# CapstoneGroup9.net
KiCad netlist of a schematic drawn in EAGLE
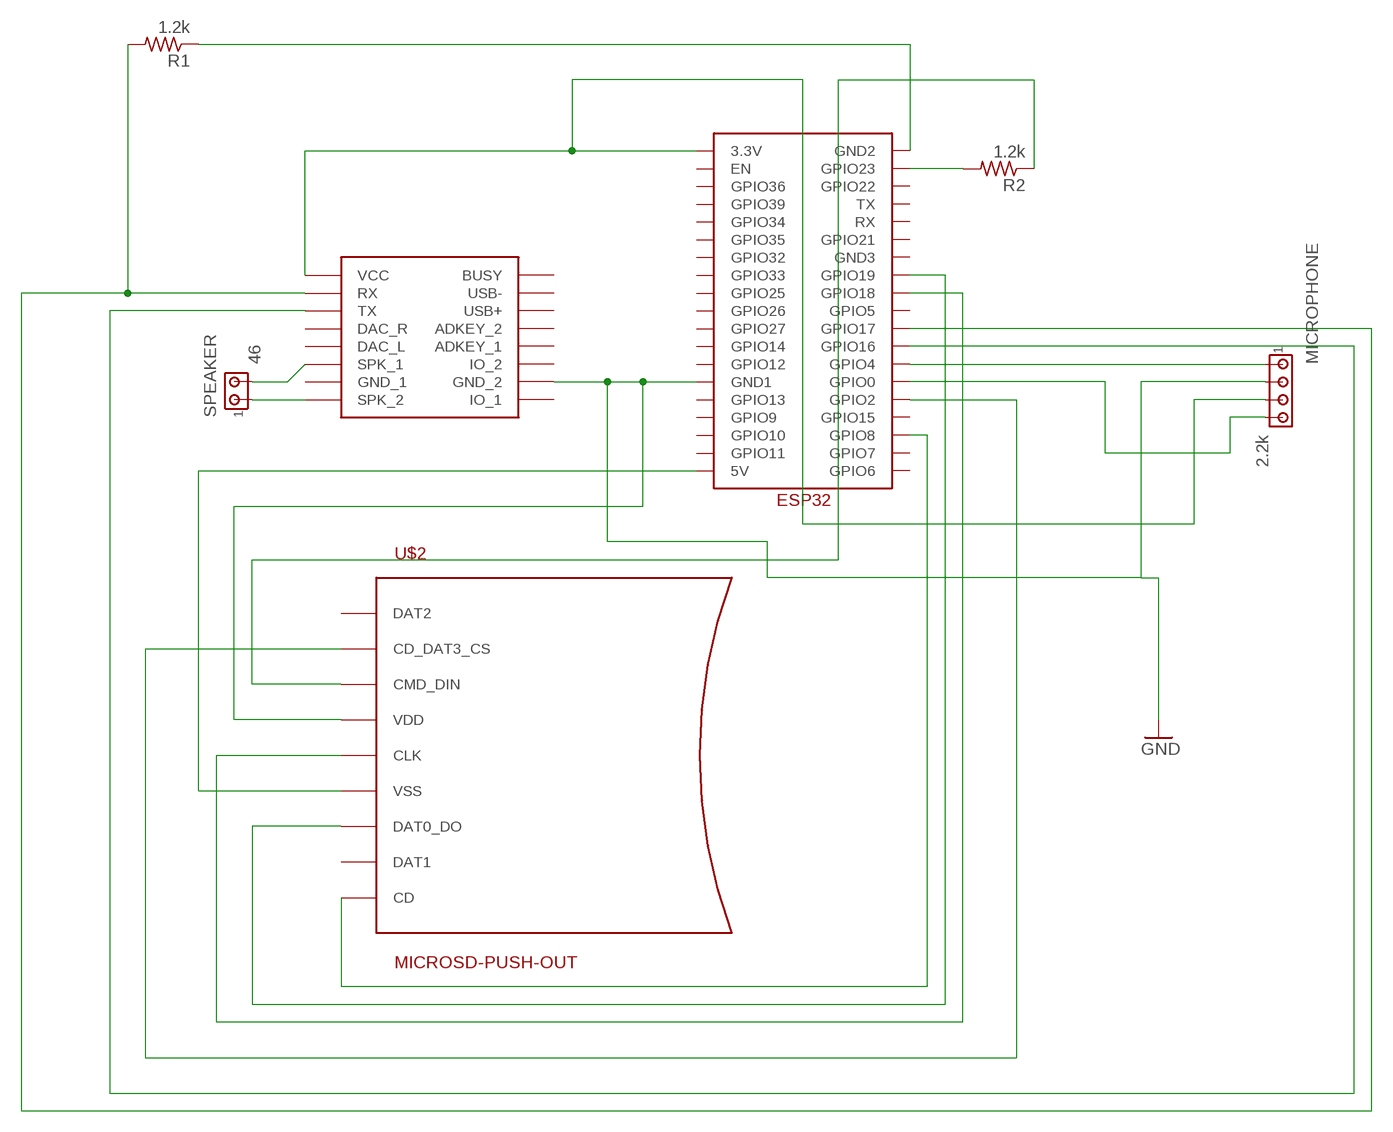
[diagram p0: schematic, sheet 1]

(export (version "E")
  (design (tool "Eeschema 10.0.6"))
  (components
    (comp (ref "DFPLAYERMINI")
      (value "DFPLAYER")
      (footprint "eagle-import:DFPLAYER")
      (libsource (lib "eagle-import") (part "DFPLAYER"))
    )
    (comp (ref "MICROPHONE")
      (value "2.2k")
      (footprint "eagle-import:10X04MTA")
      (libsource (lib "eagle-import") (part "MTA04-100"))
    )
    (comp (ref "R1")
      (value "1.2k")
      (footprint "eagle-import:0207_10")
      (libsource (lib "eagle-import") (part "R-US_0207/10"))
    )
    (comp (ref "R2")
      (value "1.2k")
      (footprint "eagle-import:0207_10")
      (libsource (lib "eagle-import") (part "R-US_0207/10"))
    )
    (comp (ref "SPEAKER")
      (value "46")
      (footprint "eagle-import:10X02MTA")
      (libsource (lib "eagle-import") (part "MTA02-100"))
    )
    (comp (ref "U$1")
      (value "ESP32")
      (footprint "eagle-import:ESP32")
      (libsource (lib "eagle-import") (part "ESP32"))
    )
    (comp (ref "U$2")
      (value "MICROSD-PUSH-OUT")
      (footprint "eagle-import:MICROSD-PUSH-OUT")
      (libsource (lib "eagle-import") (part "MICROSD-PUSH-OUT"))
    )
  )
  (nets
    (net (code "1") (name "GND") (class "Default")
      (node (ref "DFPLAYERMINI") (pin "GND_2") (pinfunction "GND_2_GND_2") (pintype "bidirectional"))
      (node (ref "MICROPHONE") (pin "2") (pinfunction "2_2") (pintype "passive"))
      (node (ref "U$1") (pin "GND1") (pinfunction "GND1_GND1") (pintype "bidirectional"))
      (node (ref "U$2") (pin "4") (pinfunction "VDD_4") (pintype "bidirectional"))
    )
    (net (code "2") (name "Net-(DFPLAYERMINI-PadRX)") (class "Default")
      (node (ref "DFPLAYERMINI") (pin "RX") (pinfunction "RX_RX") (pintype "bidirectional"))
      (node (ref "R1") (pin "2") (pinfunction "2_2") (pintype "passive"))
      (node (ref "U$1") (pin "GPIO17") (pinfunction "GPIO17_GPIO17") (pintype "bidirectional"))
    )
    (net (code "3") (name "Net-(DFPLAYERMINI-PadTX)") (class "Default")
      (node (ref "DFPLAYERMINI") (pin "TX") (pinfunction "TX_TX") (pintype "bidirectional"))
      (node (ref "U$1") (pin "GPIO16") (pinfunction "GPIO16_GPIO16") (pintype "bidirectional"))
    )
    (net (code "4") (name "Net-(DFPLAYERMINI-PadVCC)") (class "Default")
      (node (ref "DFPLAYERMINI") (pin "VCC") (pinfunction "VCC_VCC") (pintype "bidirectional"))
      (node (ref "MICROPHONE") (pin "3") (pinfunction "3_3") (pintype "passive"))
      (node (ref "U$1") (pin "3.3V") (pinfunction "3.3V_3.3V") (pintype "bidirectional"))
    )
    (net (code "5") (name "Net-(DFPLAYERMINI-SPK_1)") (class "Default")
      (node (ref "DFPLAYERMINI") (pin "SPK1") (pinfunction "SPK_1_SPK1") (pintype "bidirectional"))
      (node (ref "SPEAKER") (pin "2") (pinfunction "2_2") (pintype "passive"))
    )
    (net (code "6") (name "Net-(DFPLAYERMINI-SPK_2)") (class "Default")
      (node (ref "DFPLAYERMINI") (pin "SPK2") (pinfunction "SPK_2_SPK2") (pintype "bidirectional"))
      (node (ref "SPEAKER") (pin "1") (pinfunction "1_1") (pintype "passive"))
    )
    (net (code "7") (name "Net-(MICROPHONE-Pad1)") (class "Default")
      (node (ref "MICROPHONE") (pin "1") (pinfunction "1_1") (pintype "passive"))
      (node (ref "U$1") (pin "GPIO4") (pinfunction "GPIO4_GPIO4") (pintype "bidirectional"))
    )
    (net (code "8") (name "Net-(MICROPHONE-Pad4)") (class "Default")
      (node (ref "MICROPHONE") (pin "4") (pinfunction "4_4") (pintype "passive"))
      (node (ref "U$1") (pin "GPIO0") (pinfunction "GPIO0_GPIO0") (pintype "bidirectional"))
    )
    (net (code "9") (name "Net-(R1-Pad1)") (class "Default")
      (node (ref "R1") (pin "1") (pinfunction "1_1") (pintype "passive"))
      (node (ref "U$1") (pin "GND2") (pinfunction "GND2_GND2") (pintype "bidirectional"))
    )
    (net (code "10") (name "Net-(R2-Pad2)") (class "Default")
      (node (ref "R2") (pin "2") (pinfunction "2_2") (pintype "passive"))
      (node (ref "U$1") (pin "GPIO23") (pinfunction "GPIO23_GPIO23") (pintype "bidirectional"))
    )
    (net (code "11") (name "Net-(U$1-Pad5V)") (class "Default")
      (node (ref "U$1") (pin "5V") (pinfunction "5V_5V") (pintype "bidirectional"))
      (node (ref "U$2") (pin "6") (pinfunction "VSS_6") (pintype "bidirectional"))
      (node (ref "U$2") (pin "G1") (pinfunction "VSS_G1") (pintype "bidirectional"))
      (node (ref "U$2") (pin "G2") (pinfunction "VSS_G2") (pintype "bidirectional"))
      (node (ref "U$2") (pin "G3") (pinfunction "VSS_G3") (pintype "bidirectional"))
      (node (ref "U$2") (pin "G4") (pinfunction "VSS_G4") (pintype "bidirectional"))
    )
    (net (code "12") (name "Net-(U$1-PadGPIO8)") (class "Default")
      (node (ref "U$1") (pin "GPIO8") (pinfunction "GPIO8_GPIO8") (pintype "bidirectional"))
      (node (ref "U$2") (pin "CD") (pinfunction "CD_CD") (pintype "bidirectional"))
    )
    (net (code "13") (name "Net-(U$2-CD_DAT3_CS)") (class "Default")
      (node (ref "U$1") (pin "GPIO2") (pinfunction "GPIO2_GPIO2") (pintype "bidirectional"))
      (node (ref "U$2") (pin "2") (pinfunction "CD_DAT3_CS_2") (pintype "bidirectional"))
    )
    (net (code "14") (name "Net-(U$2-CLK)") (class "Default")
      (node (ref "U$1") (pin "GPIO18") (pinfunction "GPIO18_GPIO18") (pintype "bidirectional"))
      (node (ref "U$2") (pin "5") (pinfunction "CLK_5") (pintype "bidirectional"))
    )
    (net (code "15") (name "Net-(U$2-CMD_DIN)") (class "Default")
      (node (ref "R2") (pin "1") (pinfunction "1_1") (pintype "passive"))
      (node (ref "U$2") (pin "3") (pinfunction "CMD_DIN_3") (pintype "bidirectional"))
    )
    (net (code "16") (name "Net-(U$2-DAT0_DO)") (class "Default")
      (node (ref "U$1") (pin "GPIO19") (pinfunction "GPIO19_GPIO19") (pintype "bidirectional"))
      (node (ref "U$2") (pin "7") (pinfunction "DAT0_DO_7") (pintype "bidirectional"))
    )
    (net (code "17") (name "unconnected-(DFPLAYERMINI-ADKEY_1-PadADKEY1)") (class "Default")
      (node (ref "DFPLAYERMINI") (pin "ADKEY1") (pinfunction "ADKEY_1_ADKEY1") (pintype "bidirectional"))
    )
    (net (code "18") (name "unconnected-(DFPLAYERMINI-ADKEY_2-PadADKEY2)") (class "Default")
      (node (ref "DFPLAYERMINI") (pin "ADKEY2") (pinfunction "ADKEY_2_ADKEY2") (pintype "bidirectional"))
    )
    (net (code "19") (name "unconnected-(DFPLAYERMINI-IO_1-PadIO1)") (class "Default")
      (node (ref "DFPLAYERMINI") (pin "IO1") (pinfunction "IO_1_IO1") (pintype "bidirectional"))
    )
    (net (code "20") (name "unconnected-(DFPLAYERMINI-IO_2-PadIO2)") (class "Default")
      (node (ref "DFPLAYERMINI") (pin "IO2") (pinfunction "IO_2_IO2") (pintype "bidirectional"))
    )
    (net (code "21") (name "unconnected-(DFPLAYERMINI-PadBUSY)") (class "Default")
      (node (ref "DFPLAYERMINI") (pin "BUSY") (pinfunction "BUSY_BUSY") (pintype "bidirectional"))
    )
    (net (code "22") (name "unconnected-(DFPLAYERMINI-PadDAC_L)") (class "Default")
      (node (ref "DFPLAYERMINI") (pin "DAC_L") (pinfunction "DAC_L_DAC_L") (pintype "bidirectional"))
    )
    (net (code "23") (name "unconnected-(DFPLAYERMINI-PadDAC_R)") (class "Default")
      (node (ref "DFPLAYERMINI") (pin "DAC_R") (pinfunction "DAC_R_DAC_R") (pintype "bidirectional"))
    )
    (net (code "24") (name "unconnected-(DFPLAYERMINI-PadGND_1)") (class "Default")
      (node (ref "DFPLAYERMINI") (pin "GND_1") (pinfunction "GND_1_GND_1") (pintype "bidirectional"))
    )
    (net (code "25") (name "unconnected-(DFPLAYERMINI-PadUSB+)") (class "Default")
      (node (ref "DFPLAYERMINI") (pin "USB+") (pinfunction "USB+_USB+") (pintype "bidirectional"))
    )
    (net (code "26") (name "unconnected-(DFPLAYERMINI-PadUSB-)") (class "Default")
      (node (ref "DFPLAYERMINI") (pin "USB-") (pinfunction "USB-_USB-") (pintype "bidirectional"))
    )
    (net (code "27") (name "unconnected-(U$1-PadEN)") (class "Default")
      (node (ref "U$1") (pin "EN") (pinfunction "EN_EN") (pintype "bidirectional"))
    )
    (net (code "28") (name "unconnected-(U$1-PadGND3)") (class "Default")
      (node (ref "U$1") (pin "GND3") (pinfunction "GND3_GND3") (pintype "bidirectional"))
    )
    (net (code "29") (name "unconnected-(U$1-PadGPIO5)") (class "Default")
      (node (ref "U$1") (pin "GPIO5") (pinfunction "GPIO5_GPIO5") (pintype "bidirectional"))
    )
    (net (code "30") (name "unconnected-(U$1-PadGPIO6)") (class "Default")
      (node (ref "U$1") (pin "GPIO6") (pinfunction "GPIO6_GPIO6") (pintype "bidirectional"))
    )
    (net (code "31") (name "unconnected-(U$1-PadGPIO7)") (class "Default")
      (node (ref "U$1") (pin "GPIO7") (pinfunction "GPIO7_GPIO7") (pintype "bidirectional"))
    )
    (net (code "32") (name "unconnected-(U$1-PadGPIO9)") (class "Default")
      (node (ref "U$1") (pin "GPIO9") (pinfunction "GPIO9_GPIO9") (pintype "bidirectional"))
    )
    (net (code "33") (name "unconnected-(U$1-PadGPIO10)") (class "Default")
      (node (ref "U$1") (pin "GPIO10") (pinfunction "GPIO10_GPIO10") (pintype "bidirectional"))
    )
    (net (code "34") (name "unconnected-(U$1-PadGPIO11)") (class "Default")
      (node (ref "U$1") (pin "GPIO11") (pinfunction "GPIO11_GPIO11") (pintype "bidirectional"))
    )
    (net (code "35") (name "unconnected-(U$1-PadGPIO12)") (class "Default")
      (node (ref "U$1") (pin "GPIO12") (pinfunction "GPIO12_GPIO12") (pintype "bidirectional"))
    )
    (net (code "36") (name "unconnected-(U$1-PadGPIO13)") (class "Default")
      (node (ref "U$1") (pin "GPIO13") (pinfunction "GPIO13_GPIO13") (pintype "bidirectional"))
    )
    (net (code "37") (name "unconnected-(U$1-PadGPIO14)") (class "Default")
      (node (ref "U$1") (pin "GPIO14") (pinfunction "GPIO14_GPIO14") (pintype "bidirectional"))
    )
    (net (code "38") (name "unconnected-(U$1-PadGPIO15)") (class "Default")
      (node (ref "U$1") (pin "GPIO15") (pinfunction "GPIO15_GPIO15") (pintype "bidirectional"))
    )
    (net (code "39") (name "unconnected-(U$1-PadGPIO21)") (class "Default")
      (node (ref "U$1") (pin "GPIO21") (pinfunction "GPIO21_GPIO21") (pintype "bidirectional"))
    )
    (net (code "40") (name "unconnected-(U$1-PadGPIO22)") (class "Default")
      (node (ref "U$1") (pin "GPIO22") (pinfunction "GPIO22_GPIO22") (pintype "bidirectional"))
    )
    (net (code "41") (name "unconnected-(U$1-PadGPIO25)") (class "Default")
      (node (ref "U$1") (pin "GPIO25") (pinfunction "GPIO25_GPIO25") (pintype "bidirectional"))
    )
    (net (code "42") (name "unconnected-(U$1-PadGPIO26)") (class "Default")
      (node (ref "U$1") (pin "GPIO26") (pinfunction "GPIO26_GPIO26") (pintype "bidirectional"))
    )
    (net (code "43") (name "unconnected-(U$1-PadGPIO27)") (class "Default")
      (node (ref "U$1") (pin "GPIO27") (pinfunction "GPIO27_GPIO27") (pintype "bidirectional"))
    )
    (net (code "44") (name "unconnected-(U$1-PadGPIO32)") (class "Default")
      (node (ref "U$1") (pin "GPIO32") (pinfunction "GPIO32_GPIO32") (pintype "bidirectional"))
    )
    (net (code "45") (name "unconnected-(U$1-PadGPIO33)") (class "Default")
      (node (ref "U$1") (pin "GPIO33") (pinfunction "GPIO33_GPIO33") (pintype "bidirectional"))
    )
    (net (code "46") (name "unconnected-(U$1-PadGPIO34)") (class "Default")
      (node (ref "U$1") (pin "GPIO34") (pinfunction "GPIO34_GPIO34") (pintype "bidirectional"))
    )
    (net (code "47") (name "unconnected-(U$1-PadGPIO35)") (class "Default")
      (node (ref "U$1") (pin "GPIO35") (pinfunction "GPIO35_GPIO35") (pintype "bidirectional"))
    )
    (net (code "48") (name "unconnected-(U$1-PadGPIO36)") (class "Default")
      (node (ref "U$1") (pin "GPIO36") (pinfunction "GPIO36_GPIO36") (pintype "bidirectional"))
    )
    (net (code "49") (name "unconnected-(U$1-PadGPIO39)") (class "Default")
      (node (ref "U$1") (pin "GPIO39") (pinfunction "GPIO39_GPIO39") (pintype "bidirectional"))
    )
    (net (code "50") (name "unconnected-(U$1-PadRX)") (class "Default")
      (node (ref "U$1") (pin "RX") (pinfunction "RX_RX") (pintype "bidirectional"))
    )
    (net (code "51") (name "unconnected-(U$1-PadTX)") (class "Default")
      (node (ref "U$1") (pin "TX") (pinfunction "TX_TX") (pintype "bidirectional"))
    )
    (net (code "52") (name "unconnected-(U$2-DAT1-Pad8)") (class "Default")
      (node (ref "U$2") (pin "8") (pinfunction "DAT1_8") (pintype "bidirectional"))
    )
    (net (code "53") (name "unconnected-(U$2-DAT2-Pad1)") (class "Default")
      (node (ref "U$2") (pin "1") (pinfunction "DAT2_1") (pintype "bidirectional"))
    )
  )
)
